# SM3320-BATT-EV.net
KiCad netlist of a schematic drawn in Altium Designer
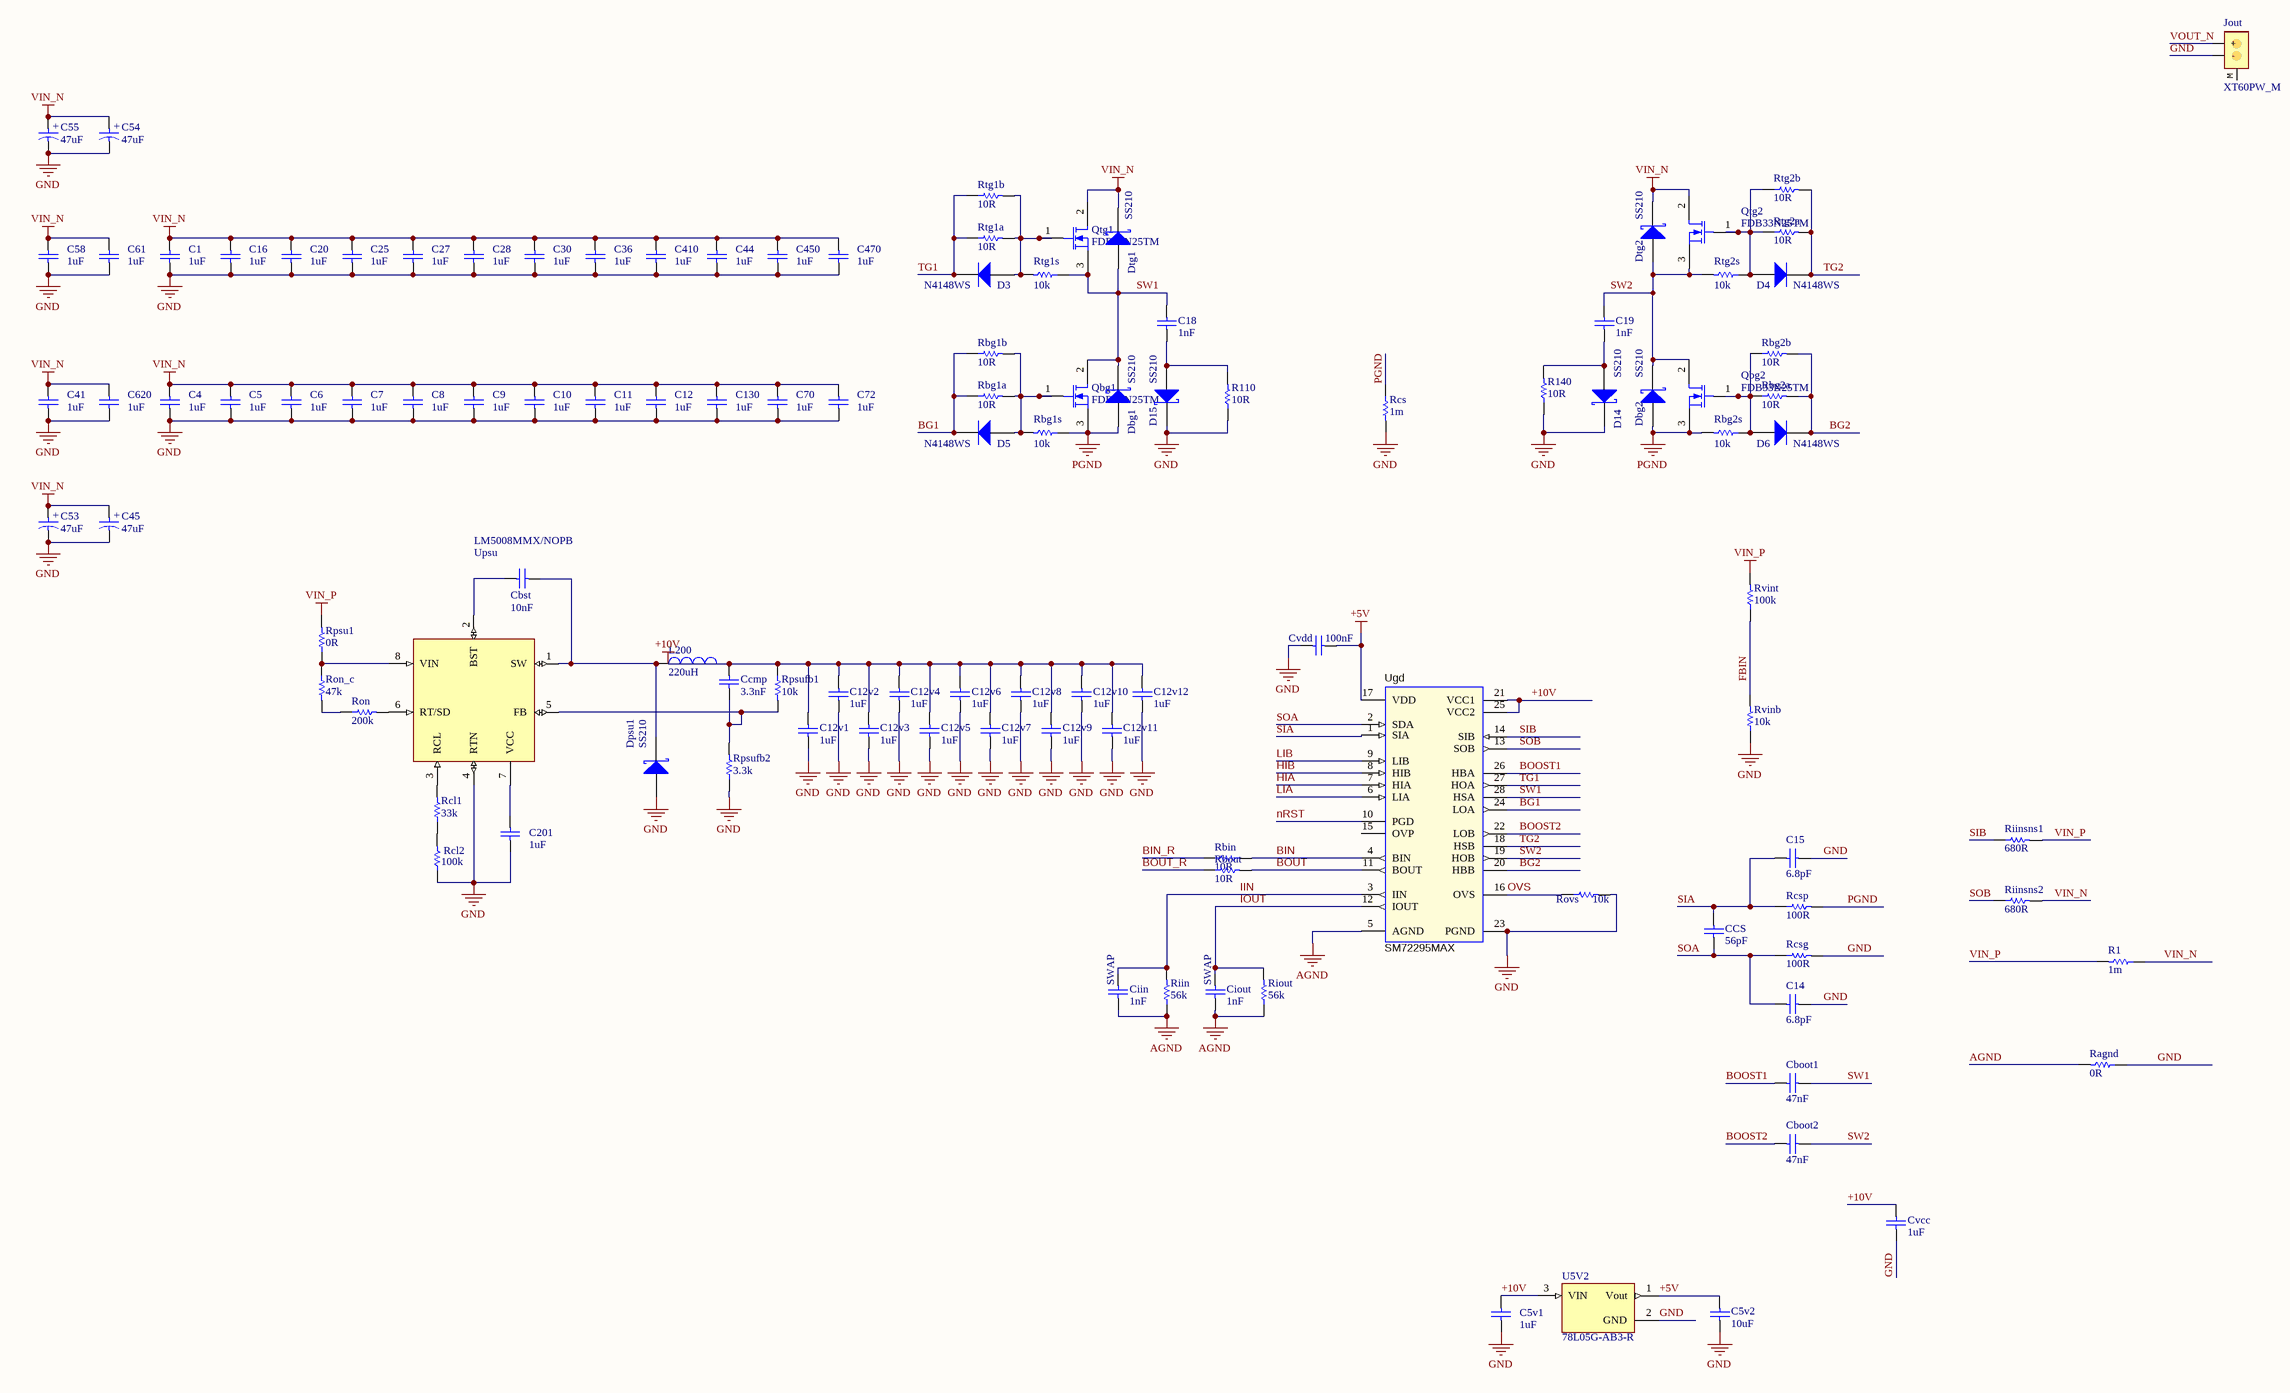
[diagram p0: SM3320-BATT-EV.SchDoc]

(export (version "E")
  (design (tool "Eeschema 10.0.6"))
  (components
    (comp (ref "C1")
      (value "1uF")
      (footprint "C_1206")
      (description "C - CAPACITOR - MLCC - 1uF - 100V - 1206 - X7R")
      (fields (field (name "LCSC PART #") "C91151") (field (name "Comment") "1206B105K101NT"))
      (libsource (lib "JLC_PCB") (part "1206B105K101NT"))
    )
    (comp (ref "C4")
      (value "1uF")
      (footprint "C_1206")
      (description "C - CAPACITOR - MLCC - 1uF - 100V - 1206 - X7R")
      (fields (field (name "LCSC PART #") "C91151") (field (name "Comment") "1206B105K101NT"))
      (libsource (lib "JLC_PCB") (part "1206B105K101NT"))
    )
    (comp (ref "C5")
      (value "1uF")
      (footprint "C_1206")
      (description "C - CAPACITOR - MLCC - 1uF - 100V - 1206 - X7R")
      (fields (field (name "LCSC PART #") "C91151") (field (name "Comment") "1206B105K101NT"))
      (libsource (lib "JLC_PCB") (part "1206B105K101NT"))
    )
    (comp (ref "C5v1")
      (value "1uF")
      (footprint "C_0402")
      (description "C - CAPACITOR - MLCC - 1uF - 25V - 0402")
      (fields (field (name "LCSC PART #") "C52923") (field (name "Comment") "CL05A105KA5NQNC"))
      (libsource (lib "JLC_PCB") (part "CL05A105KA5NQNC"))
    )
    (comp (ref "C5v2")
      (value "10uF")
      (footprint "C_0402")
      (description "C - CAPACITOR - MLCC - 10uF - 6.3V - 0402")
      (fields (field (name "LCSC PART #") "C15525") (field (name "Comment") "CL05A106MQ5NUNC"))
      (libsource (lib "JLC_PCB") (part "CL05A106MQ5NUNC"))
    )
    (comp (ref "C6")
      (value "1uF")
      (footprint "C_1206")
      (description "C - CAPACITOR - MLCC - 1uF - 100V - 1206 - X7R")
      (fields (field (name "LCSC PART #") "C91151") (field (name "Comment") "1206B105K101NT"))
      (libsource (lib "JLC_PCB") (part "1206B105K101NT"))
    )
    (comp (ref "C7")
      (value "1uF")
      (footprint "C_1206")
      (description "C - CAPACITOR - MLCC - 1uF - 100V - 1206 - X7R")
      (fields (field (name "LCSC PART #") "C91151") (field (name "Comment") "1206B105K101NT"))
      (libsource (lib "JLC_PCB") (part "1206B105K101NT"))
    )
    (comp (ref "C8")
      (value "1uF")
      (footprint "C_1206")
      (description "C - CAPACITOR - MLCC - 1uF - 100V - 1206 - X7R")
      (fields (field (name "LCSC PART #") "C91151") (field (name "Comment") "1206B105K101NT"))
      (libsource (lib "JLC_PCB") (part "1206B105K101NT"))
    )
    (comp (ref "C9")
      (value "1uF")
      (footprint "C_1206")
      (description "C - CAPACITOR - MLCC - 1uF - 100V - 1206 - X7R")
      (fields (field (name "LCSC PART #") "C91151") (field (name "Comment") "1206B105K101NT"))
      (libsource (lib "JLC_PCB") (part "1206B105K101NT"))
    )
    (comp (ref "C10")
      (value "1uF")
      (footprint "C_1206")
      (description "C - CAPACITOR - MLCC - 1uF - 100V - 1206 - X7R")
      (fields (field (name "LCSC PART #") "C91151") (field (name "Comment") "1206B105K101NT"))
      (libsource (lib "JLC_PCB") (part "1206B105K101NT"))
    )
    (comp (ref "C11")
      (value "1uF")
      (footprint "C_1206")
      (description "C - CAPACITOR - MLCC - 1uF - 100V - 1206 - X7R")
      (fields (field (name "LCSC PART #") "C91151") (field (name "Comment") "1206B105K101NT"))
      (libsource (lib "JLC_PCB") (part "1206B105K101NT"))
    )
    (comp (ref "C12")
      (value "1uF")
      (footprint "C_1206")
      (description "C - CAPACITOR - MLCC - 1uF - 100V - 1206 - X7R")
      (fields (field (name "LCSC PART #") "C91151") (field (name "Comment") "1206B105K101NT"))
      (libsource (lib "JLC_PCB") (part "1206B105K101NT"))
    )
    (comp (ref "C12v1")
      (value "1uF")
      (footprint "C_0402")
      (description "C - CAPACITOR - MLCC - 1uF - 25V - 0402")
      (fields (field (name "LCSC PART #") "C52923") (field (name "Comment") "CL05A105KA5NQNC"))
      (libsource (lib "JLC_PCB") (part "CL05A105KA5NQNC"))
    )
    (comp (ref "C12v2")
      (value "1uF")
      (footprint "C_0402")
      (description "C - CAPACITOR - MLCC - 1uF - 25V - 0402")
      (fields (field (name "LCSC PART #") "C52923") (field (name "Comment") "CL05A105KA5NQNC"))
      (libsource (lib "JLC_PCB") (part "CL05A105KA5NQNC"))
    )
    (comp (ref "C12v3")
      (value "1uF")
      (footprint "C_0402")
      (description "C - CAPACITOR - MLCC - 1uF - 25V - 0402")
      (fields (field (name "LCSC PART #") "C52923") (field (name "Comment") "CL05A105KA5NQNC"))
      (libsource (lib "JLC_PCB") (part "CL05A105KA5NQNC"))
    )
    (comp (ref "C12v4")
      (value "1uF")
      (footprint "C_0402")
      (description "C - CAPACITOR - MLCC - 1uF - 25V - 0402")
      (fields (field (name "LCSC PART #") "C52923") (field (name "Comment") "CL05A105KA5NQNC"))
      (libsource (lib "JLC_PCB") (part "CL05A105KA5NQNC"))
    )
    (comp (ref "C12v5")
      (value "1uF")
      (footprint "C_0402")
      (description "C - CAPACITOR - MLCC - 1uF - 25V - 0402")
      (fields (field (name "LCSC PART #") "C52923") (field (name "Comment") "CL05A105KA5NQNC"))
      (libsource (lib "JLC_PCB") (part "CL05A105KA5NQNC"))
    )
    (comp (ref "C12v6")
      (value "1uF")
      (footprint "C_0402")
      (description "C - CAPACITOR - MLCC - 1uF - 25V - 0402")
      (fields (field (name "LCSC PART #") "C52923") (field (name "Comment") "CL05A105KA5NQNC"))
      (libsource (lib "JLC_PCB") (part "CL05A105KA5NQNC"))
    )
    (comp (ref "C12v7")
      (value "1uF")
      (footprint "C_0402")
      (description "C - CAPACITOR - MLCC - 1uF - 25V - 0402")
      (fields (field (name "LCSC PART #") "C52923") (field (name "Comment") "CL05A105KA5NQNC"))
      (libsource (lib "JLC_PCB") (part "CL05A105KA5NQNC"))
    )
    (comp (ref "C12v8")
      (value "1uF")
      (footprint "C_0402")
      (description "C - CAPACITOR - MLCC - 1uF - 25V - 0402")
      (fields (field (name "LCSC PART #") "C52923") (field (name "Comment") "CL05A105KA5NQNC"))
      (libsource (lib "JLC_PCB") (part "CL05A105KA5NQNC"))
    )
    (comp (ref "C12v9")
      (value "1uF")
      (footprint "C_0402")
      (description "C - CAPACITOR - MLCC - 1uF - 25V - 0402")
      (fields (field (name "LCSC PART #") "C52923") (field (name "Comment") "CL05A105KA5NQNC"))
      (libsource (lib "JLC_PCB") (part "CL05A105KA5NQNC"))
    )
    (comp (ref "C12v10")
      (value "1uF")
      (footprint "C_0402")
      (description "C - CAPACITOR - MLCC - 1uF - 25V - 0402")
      (fields (field (name "LCSC PART #") "C52923") (field (name "Comment") "CL05A105KA5NQNC"))
      (libsource (lib "JLC_PCB") (part "CL05A105KA5NQNC"))
    )
    (comp (ref "C12v11")
      (value "1uF")
      (footprint "C_0402")
      (description "C - CAPACITOR - MLCC - 1uF - 25V - 0402")
      (fields (field (name "LCSC PART #") "C52923") (field (name "Comment") "CL05A105KA5NQNC"))
      (libsource (lib "JLC_PCB") (part "CL05A105KA5NQNC"))
    )
    (comp (ref "C12v12")
      (value "1uF")
      (footprint "C_0402")
      (description "C - CAPACITOR - MLCC - 1uF - 25V - 0402")
      (fields (field (name "LCSC PART #") "C52923") (field (name "Comment") "CL05A105KA5NQNC"))
      (libsource (lib "JLC_PCB") (part "CL05A105KA5NQNC"))
    )
    (comp (ref "C14")
      (value "6.8pF")
      (footprint "C_0402")
      (description "C - CAPACITOR - MLCC - 6.8pF - 50V - 0402")
      (fields (field (name "LCSC PART #") "C1576") (field (name "Comment") "0402CG6R8C500NT"))
      (libsource (lib "JLC_PCB") (part "0402CG6R8C500NT"))
    )
    (comp (ref "C15")
      (value "6.8pF")
      (footprint "C_0402")
      (description "C - CAPACITOR - MLCC - 6.8pF - 50V - 0402")
      (fields (field (name "LCSC PART #") "C1576") (field (name "Comment") "0402CG6R8C500NT"))
      (libsource (lib "JLC_PCB") (part "0402CG6R8C500NT"))
    )
    (comp (ref "C16")
      (value "1uF")
      (footprint "C_1206")
      (description "C - CAPACITOR - MLCC - 1uF - 100V - 1206 - X7R")
      (fields (field (name "LCSC PART #") "C91151") (field (name "Comment") "1206B105K101NT"))
      (libsource (lib "JLC_PCB") (part "1206B105K101NT"))
    )
    (comp (ref "C18")
      (value "1nF")
      (footprint "C_1206")
      (description "C - CAPACITOR - MLCC - 1nF - 2000V - 1206 - X7R")
      (fields (field (name "LCSC PART #") "C9196") (field (name "Comment") "1206B102K202NT"))
      (libsource (lib "JLC_PCB") (part "1206B102K202NT"))
    )
    (comp (ref "C19")
      (value "1nF")
      (footprint "C_1206")
      (description "C - CAPACITOR - MLCC - 1nF - 2000V - 1206 - X7R")
      (fields (field (name "LCSC PART #") "C9196") (field (name "Comment") "1206B102K202NT"))
      (libsource (lib "JLC_PCB") (part "1206B102K202NT"))
    )
    (comp (ref "C20")
      (value "1uF")
      (footprint "C_1206")
      (description "C - CAPACITOR - MLCC - 1uF - 100V - 1206 - X7R")
      (fields (field (name "LCSC PART #") "C91151") (field (name "Comment") "1206B105K101NT"))
      (libsource (lib "JLC_PCB") (part "1206B105K101NT"))
    )
    (comp (ref "C25")
      (value "1uF")
      (footprint "C_1206")
      (description "C - CAPACITOR - MLCC - 1uF - 100V - 1206 - X7R")
      (fields (field (name "LCSC PART #") "C91151") (field (name "Comment") "1206B105K101NT"))
      (libsource (lib "JLC_PCB") (part "1206B105K101NT"))
    )
    (comp (ref "C27")
      (value "1uF")
      (footprint "C_1206")
      (description "C - CAPACITOR - MLCC - 1uF - 100V - 1206 - X7R")
      (fields (field (name "LCSC PART #") "C91151") (field (name "Comment") "1206B105K101NT"))
      (libsource (lib "JLC_PCB") (part "1206B105K101NT"))
    )
    (comp (ref "C28")
      (value "1uF")
      (footprint "C_1206")
      (description "C - CAPACITOR - MLCC - 1uF - 100V - 1206 - X7R")
      (fields (field (name "LCSC PART #") "C91151") (field (name "Comment") "1206B105K101NT"))
      (libsource (lib "JLC_PCB") (part "1206B105K101NT"))
    )
    (comp (ref "C30")
      (value "1uF")
      (footprint "C_1206")
      (description "C - CAPACITOR - MLCC - 1uF - 100V - 1206 - X7R")
      (fields (field (name "LCSC PART #") "C91151") (field (name "Comment") "1206B105K101NT"))
      (libsource (lib "JLC_PCB") (part "1206B105K101NT"))
    )
    (comp (ref "C36")
      (value "1uF")
      (footprint "C_1206")
      (description "C - CAPACITOR - MLCC - 1uF - 100V - 1206 - X7R")
      (fields (field (name "LCSC PART #") "C91151") (field (name "Comment") "1206B105K101NT"))
      (libsource (lib "JLC_PCB") (part "1206B105K101NT"))
    )
    (comp (ref "C41")
      (value "1uF")
      (footprint "C_1206")
      (description "C - CAPACITOR - MLCC - 1uF - 100V - 1206 - X7R")
      (fields (field (name "LCSC PART #") "C91151") (field (name "Comment") "1206B105K101NT"))
      (libsource (lib "JLC_PCB") (part "1206B105K101NT"))
    )
    (comp (ref "C44")
      (value "1uF")
      (footprint "C_1206")
      (description "C - CAPACITOR - MLCC - 1uF - 100V - 1206 - X7R")
      (fields (field (name "LCSC PART #") "C91151") (field (name "Comment") "1206B105K101NT"))
      (libsource (lib "JLC_PCB") (part "1206B105K101NT"))
    )
    (comp (ref "C45")
      (value "47uF")
      (footprint "C_CAN_1010")
      (description "C - CAPACITOR - ELECTROLYTIC - 47uF - 100V")
      (fields (field (name "LCSC PART #") "C164068") (field (name "Comment") "VZH470M2ATR-1010"))
      (libsource (lib "JLC_PCB") (part "VZH470M2ATR-1010"))
    )
    (comp (ref "C53")
      (value "47uF")
      (footprint "C_CAN_1010")
      (description "C - CAPACITOR - ELECTROLYTIC - 47uF - 100V")
      (fields (field (name "LCSC PART #") "C164068") (field (name "Comment") "VZH470M2ATR-1010"))
      (libsource (lib "JLC_PCB") (part "VZH470M2ATR-1010"))
    )
    (comp (ref "C54")
      (value "47uF")
      (footprint "C_CAN_1010")
      (description "C - CAPACITOR - ELECTROLYTIC - 47uF - 100V")
      (fields (field (name "LCSC PART #") "C164068") (field (name "Comment") "VZH470M2ATR-1010"))
      (libsource (lib "JLC_PCB") (part "VZH470M2ATR-1010"))
    )
    (comp (ref "C55")
      (value "47uF")
      (footprint "C_CAN_1010")
      (description "C - CAPACITOR - ELECTROLYTIC - 47uF - 100V")
      (fields (field (name "LCSC PART #") "C164068") (field (name "Comment") "VZH470M2ATR-1010"))
      (libsource (lib "JLC_PCB") (part "VZH470M2ATR-1010"))
    )
    (comp (ref "C58")
      (value "1uF")
      (footprint "C_1206")
      (description "C - CAPACITOR - MLCC - 1uF - 100V - 1206 - X7R")
      (fields (field (name "LCSC PART #") "C91151") (field (name "Comment") "1206B105K101NT"))
      (libsource (lib "JLC_PCB") (part "1206B105K101NT"))
    )
    (comp (ref "C61")
      (value "1uF")
      (footprint "C_1206")
      (description "C - CAPACITOR - MLCC - 1uF - 100V - 1206 - X7R")
      (fields (field (name "LCSC PART #") "C91151") (field (name "Comment") "1206B105K101NT"))
      (libsource (lib "JLC_PCB") (part "1206B105K101NT"))
    )
    (comp (ref "C70")
      (value "1uF")
      (footprint "C_1206")
      (description "C - CAPACITOR - MLCC - 1uF - 100V - 1206 - X7R")
      (fields (field (name "LCSC PART #") "C91151") (field (name "Comment") "1206B105K101NT"))
      (libsource (lib "JLC_PCB") (part "1206B105K101NT"))
    )
    (comp (ref "C72")
      (value "1uF")
      (footprint "C_1206")
      (description "C - CAPACITOR - MLCC - 1uF - 100V - 1206 - X7R")
      (fields (field (name "LCSC PART #") "C91151") (field (name "Comment") "1206B105K101NT"))
      (libsource (lib "JLC_PCB") (part "1206B105K101NT"))
    )
    (comp (ref "C130")
      (value "1uF")
      (footprint "C_1206")
      (description "C - CAPACITOR - MLCC - 1uF - 100V - 1206 - X7R")
      (fields (field (name "LCSC PART #") "C91151") (field (name "Comment") "1206B105K101NT"))
      (libsource (lib "JLC_PCB") (part "1206B105K101NT"))
    )
    (comp (ref "C201")
      (value "1uF")
      (footprint "C_0402")
      (description "C - CAPACITOR - MLCC - 1uF - 25V - 0402")
      (fields (field (name "LCSC PART #") "C52923") (field (name "Comment") "CL05A105KA5NQNC"))
      (libsource (lib "JLC_PCB") (part "CL05A105KA5NQNC"))
    )
    (comp (ref "C410")
      (value "1uF")
      (footprint "C_1206")
      (description "C - CAPACITOR - MLCC - 1uF - 100V - 1206 - X7R")
      (fields (field (name "LCSC PART #") "C91151") (field (name "Comment") "1206B105K101NT"))
      (libsource (lib "JLC_PCB") (part "1206B105K101NT"))
    )
    (comp (ref "C450")
      (value "1uF")
      (footprint "C_1206")
      (description "C - CAPACITOR - MLCC - 1uF - 100V - 1206 - X7R")
      (fields (field (name "LCSC PART #") "C91151") (field (name "Comment") "1206B105K101NT"))
      (libsource (lib "JLC_PCB") (part "1206B105K101NT"))
    )
    (comp (ref "C470")
      (value "1uF")
      (footprint "C_1206")
      (description "C - CAPACITOR - MLCC - 1uF - 100V - 1206 - X7R")
      (fields (field (name "LCSC PART #") "C91151") (field (name "Comment") "1206B105K101NT"))
      (libsource (lib "JLC_PCB") (part "1206B105K101NT"))
    )
    (comp (ref "C620")
      (value "1uF")
      (footprint "C_1206")
      (description "C - CAPACITOR - MLCC - 1uF - 100V - 1206 - X7R")
      (fields (field (name "LCSC PART #") "C91151") (field (name "Comment") "1206B105K101NT"))
      (libsource (lib "JLC_PCB") (part "1206B105K101NT"))
    )
    (comp (ref "Cboot1")
      (value "47nF")
      (footprint "C_0603")
      (description "C - CAPACITOR - MLCC - 470nF - 25V - 0603")
      (fields (field (name "LCSC PART #") "C1623") (field (name "Comment") "CL10B474KA8NNNC"))
      (libsource (lib "JLC_PCB") (part "CL10B474KA8NNNC"))
    )
    (comp (ref "Cboot2")
      (value "47nF")
      (footprint "C_0603")
      (description "C - CAPACITOR - MLCC - 470nF - 25V - 0603")
      (fields (field (name "LCSC PART #") "C1623") (field (name "Comment") "CL10B474KA8NNNC"))
      (libsource (lib "JLC_PCB") (part "CL10B474KA8NNNC"))
    )
    (comp (ref "Cbst")
      (value "10nF")
      (footprint "C_0402")
      (description "C - CAPACITOR - MLCC - 10nF - 50V - 0402")
      (fields (field (name "LCSC PART #") "C15195") (field (name "Comment") "CL05B103KB5NNNC"))
      (libsource (lib "JLC_PCB") (part "CL05B103KB5NNNC"))
    )
    (comp (ref "Ccmp")
      (value "3.3nF")
      (footprint "C_0402")
      (description "C - CAPACITOR - MLCC - 3.3nF - 50V - 0402")
      (fields (field (name "LCSC PART #") "C26404") (field (name "Comment") "CL05B332KB5NNNC"))
      (libsource (lib "JLC_PCB") (part "CL05B332KB5NNNC"))
    )
    (comp (ref "CCS")
      (value "56pF")
      (footprint "C_0402")
      (description "C - CAPACITOR - MLCC - 56pF - 50V -  0402")
      (fields (field (name "LCSC PART #") "C1572") (field (name "Comment") "0402CG560J500NT"))
      (libsource (lib "JLC_PCB") (part "0402CG560J500NT"))
    )
    (comp (ref "Ciin")
      (value "1nF")
      (footprint "C_0402")
      (description "C - CAPACITOR - MLCC - 1nF - 50V - 0402")
      (fields (field (name "LCSC PART #") "C1523") (field (name "Comment") "0402B102K500NT"))
      (libsource (lib "JLC_PCB") (part "0402B102K500NT"))
    )
    (comp (ref "Ciout")
      (value "1nF")
      (footprint "C_0402")
      (description "C - CAPACITOR - MLCC - 1nF - 50V - 0402")
      (fields (field (name "LCSC PART #") "C1523") (field (name "Comment") "0402B102K500NT"))
      (libsource (lib "JLC_PCB") (part "0402B102K500NT"))
    )
    (comp (ref "Cvcc")
      (value "1uF")
      (footprint "C_0402")
      (description "C - CAPACITOR - MLCC - 1uF - 25V - 0402")
      (fields (field (name "LCSC PART #") "C52923") (field (name "Comment") "CL05A105KA5NQNC"))
      (libsource (lib "JLC_PCB") (part "CL05A105KA5NQNC"))
    )
    (comp (ref "Cvdd")
      (value "100nF")
      (footprint "C_0402")
      (description "C - CAPACITOR - MLCC - 100nF - 16V - 0402")
      (fields (field (name "LCSC PART #") "C1525") (field (name "Comment") "CL05B104KO5NNNC"))
      (libsource (lib "JLC_PCB") (part "CL05B104KO5NNNC"))
    )
    (comp (ref "D3")
      (value "N4148WS")
      (footprint "SOD-323")
      (description "D - DIODE - FAST TRR - 100V - 150mA - 4ns")
      (fields (field (name "LCSC PART #") "C2128"))
      (libsource (lib "JLC_PCB") (part "N4148WS"))
    )
    (comp (ref "D4")
      (value "N4148WS")
      (footprint "SOD-323")
      (description "D - DIODE - FAST TRR - 100V - 150mA - 4ns")
      (fields (field (name "LCSC PART #") "C2128"))
      (libsource (lib "JLC_PCB") (part "N4148WS"))
    )
    (comp (ref "D5")
      (value "N4148WS")
      (footprint "SOD-323")
      (description "D - DIODE - FAST TRR - 100V - 150mA - 4ns")
      (fields (field (name "LCSC PART #") "C2128"))
      (libsource (lib "JLC_PCB") (part "N4148WS"))
    )
    (comp (ref "D6")
      (value "N4148WS")
      (footprint "SOD-323")
      (description "D - DIODE - FAST TRR - 100V - 150mA - 4ns")
      (fields (field (name "LCSC PART #") "C2128"))
      (libsource (lib "JLC_PCB") (part "N4148WS"))
    )
    (comp (ref "D14")
      (value "SS210")
      (footprint "DO-214AC")
      (description "D - DIODE - SCHOTTKY - 100V - 2A")
      (fields (field (name "LCSC PART #") "C14996"))
      (libsource (lib "JLC_PCB") (part "SS210"))
    )
    (comp (ref "D15")
      (value "SS210")
      (footprint "DO-214AC")
      (description "D - DIODE - SCHOTTKY - 100V - 2A")
      (fields (field (name "LCSC PART #") "C14996"))
      (libsource (lib "JLC_PCB") (part "SS210"))
    )
    (comp (ref "Dbg1")
      (value "SS210")
      (footprint "DO-214AC")
      (description "D - DIODE - SCHOTTKY - 100V - 2A")
      (fields (field (name "LCSC PART #") "C14996"))
      (libsource (lib "JLC_PCB") (part "SS210"))
    )
    (comp (ref "Dbg2")
      (value "SS210")
      (footprint "DO-214AC")
      (description "D - DIODE - SCHOTTKY - 100V - 2A")
      (fields (field (name "LCSC PART #") "C14996"))
      (libsource (lib "JLC_PCB") (part "SS210"))
    )
    (comp (ref "Dpsu1")
      (value "SS210")
      (footprint "DO-214AC")
      (description "D - DIODE - SCHOTTKY - 100V - 2A")
      (fields (field (name "LCSC PART #") "C14996"))
      (libsource (lib "JLC_PCB") (part "SS210"))
    )
    (comp (ref "Dtg1")
      (value "SS210")
      (footprint "DO-214AC")
      (description "D - DIODE - SCHOTTKY - 100V - 2A")
      (fields (field (name "LCSC PART #") "C14996"))
      (libsource (lib "JLC_PCB") (part "SS210"))
    )
    (comp (ref "Dtg2")
      (value "SS210")
      (footprint "DO-214AC")
      (description "D - DIODE - SCHOTTKY - 100V - 2A")
      (fields (field (name "LCSC PART #") "C14996"))
      (libsource (lib "JLC_PCB") (part "SS210"))
    )
    (comp (ref "Jout")
      (value "XT60PW_M")
      (footprint "XT60PW_M")
      (description "J - JACK - POWER - XT60 - RIGHT - MALE")
      (fields (field (name "LCSC PART #") "X"))
      (libsource (lib "JLC_PCB") (part "XT60PW_M"))
    )
    (comp (ref "L200")
      (value "220uH")
      (footprint "SRR1260")
      (description "L - INDUCTOR - 220uH - 1.6A - 12.5mm")
      (fields (field (name "LCSC PART #") "C169380") (field (name "Comment") "SWRB1207S-221MT"))
      (libsource (lib "JLC_PCB") (part "SWRB1207S-221MT"))
    )
    (comp (ref "Qbg1")
      (value "FDB33N25TM")
      (footprint "TO-263-3")
      (description "Q - TRANSISTOR - MOSFET (N) - 250V - 33A - 0.094R")
      (fields (field (name "LCSC PART #") "C241752"))
      (libsource (lib "JLC_PCB") (part "FDB33N25TM"))
    )
    (comp (ref "Qbg2")
      (value "FDB33N25TM")
      (footprint "TO-263-3")
      (description "Q - TRANSISTOR - MOSFET (N) - 250V - 33A - 0.094R")
      (fields (field (name "LCSC PART #") "C241752"))
      (libsource (lib "JLC_PCB") (part "FDB33N25TM"))
    )
    (comp (ref "Qtg1")
      (value "FDB33N25TM")
      (footprint "TO-263-3")
      (description "Q - TRANSISTOR - MOSFET (N) - 250V - 33A - 0.094R")
      (fields (field (name "LCSC PART #") "C241752"))
      (libsource (lib "JLC_PCB") (part "FDB33N25TM"))
    )
    (comp (ref "Qtg2")
      (value "FDB33N25TM")
      (footprint "TO-263-3")
      (description "Q - TRANSISTOR - MOSFET (N) - 250V - 33A - 0.094R")
      (fields (field (name "LCSC PART #") "C241752"))
      (libsource (lib "JLC_PCB") (part "FDB33N25TM"))
    )
    (comp (ref "R1")
      (value "1m")
      (footprint "R_2512")
      (description "R - RESISTOR - SMD - 0.005R - 1% - 2512 - 2W")
      (fields (field (name "LCSC PART #") "C371096") (field (name "POWER") "2W"))
      (libsource (lib "JLC_PCB") (part "FMF25FPJR005-LH"))
    )
    (comp (ref "R110")
      (value "10R")
      (footprint "R_1206")
      (description "R - RESISTOR - SMD - 10R - 1% - 1206")
      (fields (field (name "LCSC PART #") "C17903") (field (name "Comment") "1206W4F100JT5E"))
      (libsource (lib "JLC_PCB") (part "1206W4F100JT5E"))
    )
    (comp (ref "R140")
      (value "10R")
      (footprint "R_1206")
      (description "R - RESISTOR - SMD - 10R - 1% - 1206")
      (fields (field (name "LCSC PART #") "C17903") (field (name "Comment") "1206W4F100JT5E"))
      (libsource (lib "JLC_PCB") (part "1206W4F100JT5E"))
    )
    (comp (ref "Ragnd")
      (value "0R")
      (footprint "R_0402")
      (description "R - RESISTOR - SMD - 0R - 1% - 0402")
      (fields (field (name "LCSC PART #") "C17168") (field (name "Comment") "0402WGF0000TCE"))
      (libsource (lib "JLC_PCB") (part "0402WGF0000TCE"))
    )
    (comp (ref "Rbg1a")
      (value "10R")
      (footprint "R_0402")
      (description "R - RESISTOR - SMD - 10R - 1% - 0402")
      (fields (field (name "LCSC PART #") "C25077") (field (name "Comment") "0402WGF100JTCE"))
      (libsource (lib "JLC_PCB") (part "0402WGF100JTCE"))
    )
    (comp (ref "Rbg1b")
      (value "10R")
      (footprint "R_0402")
      (description "R - RESISTOR - SMD - 10R - 1% - 0402")
      (fields (field (name "LCSC PART #") "C25077") (field (name "Comment") "0402WGF100JTCE"))
      (libsource (lib "JLC_PCB") (part "0402WGF100JTCE"))
    )
    (comp (ref "Rbg1s")
      (value "10k")
      (footprint "R_0402")
      (description "R - RESISTOR - SMD - 10k - 1% - 0402")
      (fields (field (name "LCSC PART #") "C25744") (field (name "Comment") "0402WGF1002TCE"))
      (libsource (lib "JLC_PCB") (part "0402WGF1002TCE"))
    )
    (comp (ref "Rbg2a")
      (value "10R")
      (footprint "R_0402")
      (description "R - RESISTOR - SMD - 10R - 1% - 0402")
      (fields (field (name "LCSC PART #") "C25077") (field (name "Comment") "0402WGF100JTCE"))
      (libsource (lib "JLC_PCB") (part "0402WGF100JTCE"))
    )
    (comp (ref "Rbg2b")
      (value "10R")
      (footprint "R_0402")
      (description "R - RESISTOR - SMD - 10R - 1% - 0402")
      (fields (field (name "LCSC PART #") "C25077") (field (name "Comment") "0402WGF100JTCE"))
      (libsource (lib "JLC_PCB") (part "0402WGF100JTCE"))
    )
    (comp (ref "Rbg2s")
      (value "10k")
      (footprint "R_0402")
      (description "R - RESISTOR - SMD - 10k - 1% - 0402")
      (fields (field (name "LCSC PART #") "C25744") (field (name "Comment") "0402WGF1002TCE"))
      (libsource (lib "JLC_PCB") (part "0402WGF1002TCE"))
    )
    (comp (ref "Rbin")
      (value "10R")
      (footprint "R_0402")
      (description "R - RESISTOR - SMD - 10R - 1% - 0402")
      (fields (field (name "LCSC PART #") "C25077") (field (name "Comment") "0402WGF100JTCE"))
      (libsource (lib "JLC_PCB") (part "0402WGF100JTCE"))
    )
    (comp (ref "Rbout")
      (value "10R")
      (footprint "R_0402")
      (description "R - RESISTOR - SMD - 10R - 1% - 0402")
      (fields (field (name "LCSC PART #") "C25077") (field (name "Comment") "0402WGF100JTCE"))
      (libsource (lib "JLC_PCB") (part "0402WGF100JTCE"))
    )
    (comp (ref "Rcl1")
      (value "33k")
      (footprint "R_0402")
      (description "R - RESISTOR - SMD - 33k - 1% - 0402")
      (fields (field (name "LCSC PART #") "C25779") (field (name "Comment") "0402WGF3302TCE"))
      (libsource (lib "JLC_PCB") (part "0402WGF3302TCE"))
    )
    (comp (ref "Rcl2")
      (value "100k")
      (footprint "R_0402")
      (description "R - RESISTOR - SMD - 100k - 1% -  0402")
      (fields (field (name "LCSC PART #") "C25741") (field (name "Comment") "0402WGF1003TCE"))
      (libsource (lib "JLC_PCB") (part "0402WGF1003TCE"))
    )
    (comp (ref "Rcs")
      (value "1m")
      (footprint "R_2512")
      (description "R - RESISTOR - SMD - 0.005R - 1% - 2512 - 2W")
      (fields (field (name "LCSC PART #") "C371096") (field (name "POWER") "2W"))
      (libsource (lib "JLC_PCB") (part "FMF25FPJR005-LH"))
    )
    (comp (ref "Rcsg")
      (value "100R")
      (footprint "R_0402")
      (description "R - RESISTOR - SMD - 100R - 1% - 0402")
      (fields (field (name "LCSC PART #") "C25076") (field (name "Comment") "0402WGF1000TCE"))
      (libsource (lib "JLC_PCB") (part "0402WGF1000TCE"))
    )
    (comp (ref "Rcsp")
      (value "100R")
      (footprint "R_0402")
      (description "R - RESISTOR - SMD - 100R - 1% - 0402")
      (fields (field (name "LCSC PART #") "C25076") (field (name "Comment") "0402WGF1000TCE"))
      (libsource (lib "JLC_PCB") (part "0402WGF1000TCE"))
    )
    (comp (ref "Riin")
      (value "56k")
      (footprint "R_0402")
      (description "R - RESISTOR - SMD - 56k - 1% - 0402")
      (fields (field (name "LCSC PART #") "C25796") (field (name "Comment") "0402WGF5602TCE"))
      (libsource (lib "JLC_PCB") (part "0402WGF5602TCE"))
    )
    (comp (ref "Riinsns1")
      (value "680R")
      (footprint "R_0603")
      (description "R - RESISTOR - SMD - 680R - 1% - 0603")
      (fields (field (name "LCSC PART #") "C23228") (field (name "Comment") "0603WAF6800T5E"))
      (libsource (lib "JLC_PCB") (part "0603WAF6800T5E"))
    )
    (comp (ref "Riinsns2")
      (value "680R")
      (footprint "R_0603")
      (description "R - RESISTOR - SMD - 680R - 1% - 0603")
      (fields (field (name "LCSC PART #") "C23228") (field (name "Comment") "0603WAF6800T5E"))
      (libsource (lib "JLC_PCB") (part "0603WAF6800T5E"))
    )
    (comp (ref "Riout")
      (value "56k")
      (footprint "R_0402")
      (description "R - RESISTOR - SMD - 56k - 1% - 0402")
      (fields (field (name "LCSC PART #") "C25796") (field (name "Comment") "0402WGF5602TCE"))
      (libsource (lib "JLC_PCB") (part "0402WGF5602TCE"))
    )
    (comp (ref "Ron")
      (value "200k")
      (footprint "R_0402")
      (description "R - RESISTOR - SMD - 200k - 1% - 0402")
      (fields (field (name "LCSC PART #") "C25764") (field (name "Comment") "0402WGF2003TCE"))
      (libsource (lib "JLC_PCB") (part "0402WGF2003TCE"))
    )
    (comp (ref "Ron_c")
      (value "47k")
      (footprint "R_0402")
      (description "R - RESISTOR - SMD - 47k - 1% - 0402")
      (fields (field (name "LCSC PART #") "C25792") (field (name "Comment") "0402WGF4702TCE"))
      (libsource (lib "JLC_PCB") (part "0402WGF4702TCE"))
    )
    (comp (ref "Rovs")
      (value "10k")
      (footprint "R_0402")
      (description "R - RESISTOR - SMD - 10k - 1% - 0402")
      (fields (field (name "LCSC PART #") "C25744") (field (name "Comment") "0402WGF1002TCE"))
      (libsource (lib "JLC_PCB") (part "0402WGF1002TCE"))
    )
    (comp (ref "Rpsu1")
      (value "0R")
      (footprint "R_0402")
      (description "R - RESISTOR - SMD - 0R - 1% - 0402")
      (fields (field (name "LCSC PART #") "C17168") (field (name "Comment") "0402WGF0000TCE"))
      (libsource (lib "JLC_PCB") (part "0402WGF0000TCE"))
    )
    (comp (ref "Rpsufb1")
      (value "10k")
      (footprint "R_0402")
      (description "R - RESISTOR - SMD - 10k - 1% - 0402")
      (fields (field (name "LCSC PART #") "C25744") (field (name "Comment") "0402WGF1002TCE"))
      (libsource (lib "JLC_PCB") (part "0402WGF1002TCE"))
    )
    (comp (ref "Rpsufb2")
      (value "3.3k")
      (footprint "R_0402")
      (description "R - RESISTOR - SMD - 3.3k - 1% - 0402")
      (fields (field (name "LCSC PART #") "C25890") (field (name "Comment") "0402WGF3301TCE"))
      (libsource (lib "JLC_PCB") (part "0402WGF3301TCE"))
    )
    (comp (ref "Rtg1a")
      (value "10R")
      (footprint "R_0402")
      (description "R - RESISTOR - SMD - 10R - 1% - 0402")
      (fields (field (name "LCSC PART #") "C25077") (field (name "Comment") "0402WGF100JTCE"))
      (libsource (lib "JLC_PCB") (part "0402WGF100JTCE"))
    )
    (comp (ref "Rtg1b")
      (value "10R")
      (footprint "R_0402")
      (description "R - RESISTOR - SMD - 10R - 1% - 0402")
      (fields (field (name "LCSC PART #") "C25077") (field (name "Comment") "0402WGF100JTCE"))
      (libsource (lib "JLC_PCB") (part "0402WGF100JTCE"))
    )
    (comp (ref "Rtg1s")
      (value "10k")
      (footprint "R_0402")
      (description "R - RESISTOR - SMD - 10k - 1% - 0402")
      (fields (field (name "LCSC PART #") "C25744") (field (name "Comment") "0402WGF1002TCE"))
      (libsource (lib "JLC_PCB") (part "0402WGF1002TCE"))
    )
    (comp (ref "Rtg2a")
      (value "10R")
      (footprint "R_0402")
      (description "R - RESISTOR - SMD - 10R - 1% - 0402")
      (fields (field (name "LCSC PART #") "C25077") (field (name "Comment") "0402WGF100JTCE"))
      (libsource (lib "JLC_PCB") (part "0402WGF100JTCE"))
    )
    (comp (ref "Rtg2b")
      (value "10R")
      (footprint "R_0402")
      (description "R - RESISTOR - SMD - 10R - 1% - 0402")
      (fields (field (name "LCSC PART #") "C25077") (field (name "Comment") "0402WGF100JTCE"))
      (libsource (lib "JLC_PCB") (part "0402WGF100JTCE"))
    )
    (comp (ref "Rtg2s")
      (value "10k")
      (footprint "R_0402")
      (description "R - RESISTOR - SMD - 10k - 1% - 0402")
      (fields (field (name "LCSC PART #") "C25744") (field (name "Comment") "0402WGF1002TCE"))
      (libsource (lib "JLC_PCB") (part "0402WGF1002TCE"))
    )
    (comp (ref "Rvinb")
      (value "10k")
      (footprint "R_0603")
      (description "R - RESISTOR - SMD - 10k - 1% - 0603")
      (fields (field (name "LCSC PART #") "C25804") (field (name "Comment") "0603WAF1002T5E"))
      (libsource (lib "JLC_PCB") (part "0603WAF1002T5E"))
    )
    (comp (ref "Rvint")
      (value "100k")
      (footprint "R_0603")
      (description "R - RESISTOR - SMD - 100k - 1% -  0603")
      (fields (field (name "LCSC PART #") "C22936") (field (name "Comment") "0603WAF100KT5E"))
      (libsource (lib "JLC_PCB") (part "0603WAF100KT5E"))
    )
    (comp (ref "U5V2")
      (value "78L05G-AB3-R")
      (footprint "SOT-223-3")
      (description "U - IC - 5V Power Regulator")
      (fields (field (name "LCSC PART #") "C71136"))
      (libsource (lib "JLC_PCB") (part "78L05G-AB3-R"))
    )
    (comp (ref "Ugd")
      (value "SM72295MAX")
      (footprint "M28B_M")
      (description "Photovoltaic Full Bridge Driver")
      (fields (field (name "MANUFACTURER") "National Semiconductor") (field (name "PARTNUMBER") "SM72295"))
      (libsource (lib "JLC_PCB") (part "SM72295"))
    )
    (comp (ref "Upsu")
      (value "LM5008MMX/NOPB")
      (footprint "SOP65P490X110-8N")
      (description "U - IC - BUCK CONVERTER, ADJUSTABLE, 95V, 350mA")
      (libsource (lib "JLC_PCB") (part "LM5008MMX/NOPB"))
    )
  )
  (nets
    (net (code "1") (name "+5V") (class "Default")
      (node (ref "C5v2") (pin "2") (pinfunction "2_2") (pintype "passive"))
      (node (ref "Cvdd") (pin "2") (pinfunction "2_2") (pintype "passive"))
      (node (ref "U5V2") (pin "1") (pinfunction "Vout_1") (pintype "output"))
      (node (ref "Ugd") (pin "17") (pinfunction "VDD_17") (pintype "power_in"))
    )
    (net (code "2") (name "+10V") (class "Default")
      (node (ref "C12v1") (pin "1") (pinfunction "1_1") (pintype "passive"))
      (node (ref "C12v10") (pin "1") (pinfunction "1_1") (pintype "passive"))
      (node (ref "C12v11") (pin "1") (pinfunction "1_1") (pintype "passive"))
      (node (ref "C12v12") (pin "1") (pinfunction "1_1") (pintype "passive"))
      (node (ref "C12v2") (pin "1") (pinfunction "1_1") (pintype "passive"))
      (node (ref "C12v3") (pin "1") (pinfunction "1_1") (pintype "passive"))
      (node (ref "C12v4") (pin "1") (pinfunction "1_1") (pintype "passive"))
      (node (ref "C12v5") (pin "1") (pinfunction "1_1") (pintype "passive"))
      (node (ref "C12v6") (pin "1") (pinfunction "1_1") (pintype "passive"))
      (node (ref "C12v7") (pin "1") (pinfunction "1_1") (pintype "passive"))
      (node (ref "C12v8") (pin "1") (pinfunction "1_1") (pintype "passive"))
      (node (ref "C12v9") (pin "1") (pinfunction "1_1") (pintype "passive"))
      (node (ref "C5v1") (pin "2") (pinfunction "2_2") (pintype "passive"))
      (node (ref "Ccmp") (pin "2") (pinfunction "2_2") (pintype "passive"))
      (node (ref "Cvcc") (pin "2") (pinfunction "2_2") (pintype "passive"))
      (node (ref "L200") (pin "2") (pinfunction "2_2") (pintype "passive"))
      (node (ref "Rpsufb1") (pin "1") (pinfunction "1_1") (pintype "passive"))
      (node (ref "U5V2") (pin "3") (pinfunction "VIN_3") (pintype "input"))
      (node (ref "Ugd") (pin "21") (pinfunction "VCC1_21") (pintype "power_in"))
      (node (ref "Ugd") (pin "25") (pinfunction "VCC2_25") (pintype "power_in"))
    )
    (net (code "3") (name "/BG1") (class "Default")
      (node (ref "D5") (pin "1") (pinfunction "K_1") (pintype "passive"))
      (node (ref "Rbg1a") (pin "1") (pinfunction "1_1") (pintype "passive"))
      (node (ref "Rbg1b") (pin "1") (pinfunction "1_1") (pintype "passive"))
      (node (ref "Ugd") (pin "24") (pinfunction "LOA_24") (pintype "output"))
    )
    (net (code "4") (name "/BG2") (class "Default")
      (node (ref "D6") (pin "1") (pinfunction "K_1") (pintype "passive"))
      (node (ref "Rbg2a") (pin "2") (pinfunction "2_2") (pintype "passive"))
      (node (ref "Rbg2b") (pin "2") (pinfunction "2_2") (pintype "passive"))
      (node (ref "Ugd") (pin "20") (pinfunction "HBB_20") (pintype "passive"))
    )
    (net (code "5") (name "/BIN") (class "Default")
      (node (ref "Rbin") (pin "2") (pinfunction "2_2") (pintype "passive"))
      (node (ref "Ugd") (pin "4") (pinfunction "BIN_4") (pintype "output"))
    )
    (net (code "6") (name "/BIN_R") (class "Default")
      (node (ref "Rbin") (pin "1") (pinfunction "1_1") (pintype "passive"))
    )
    (net (code "7") (name "/BOOST1") (class "Default")
      (node (ref "Cboot1") (pin "2") (pinfunction "2_2") (pintype "passive"))
      (node (ref "Ugd") (pin "26") (pinfunction "HBA_26") (pintype "passive"))
    )
    (net (code "8") (name "/BOOST2") (class "Default")
      (node (ref "Cboot2") (pin "2") (pinfunction "2_2") (pintype "passive"))
      (node (ref "Ugd") (pin "22") (pinfunction "LOB_22") (pintype "output"))
    )
    (net (code "9") (name "/BOUT") (class "Default")
      (node (ref "Rbout") (pin "2") (pinfunction "2_2") (pintype "passive"))
      (node (ref "Ugd") (pin "11") (pinfunction "BOUT_11") (pintype "output"))
    )
    (net (code "10") (name "/BOUT_R") (class "Default")
      (node (ref "Rbout") (pin "1") (pinfunction "1_1") (pintype "passive"))
    )
    (net (code "11") (name "/FBIN") (class "Default")
      (node (ref "Rvinb") (pin "2") (pinfunction "2_2") (pintype "passive"))
      (node (ref "Rvint") (pin "1") (pinfunction "1_1") (pintype "passive"))
    )
    (net (code "12") (name "/HIA") (class "Default")
      (node (ref "Ugd") (pin "7") (pinfunction "HIA_7") (pintype "input"))
    )
    (net (code "13") (name "/HIB") (class "Default")
      (node (ref "Ugd") (pin "8") (pinfunction "HIB_8") (pintype "input"))
    )
    (net (code "14") (name "/IIN") (class "Default")
      (node (ref "Ciin") (pin "2") (pinfunction "2_2") (pintype "passive"))
      (node (ref "Riin") (pin "2") (pinfunction "2_2") (pintype "passive"))
      (node (ref "Ugd") (pin "3") (pinfunction "IIN_3") (pintype "output"))
    )
    (net (code "15") (name "/IOUT") (class "Default")
      (node (ref "Ciout") (pin "2") (pinfunction "2_2") (pintype "passive"))
      (node (ref "Riout") (pin "2") (pinfunction "2_2") (pintype "passive"))
      (node (ref "Ugd") (pin "12") (pinfunction "IOUT_12") (pintype "output"))
    )
    (net (code "16") (name "/LIA") (class "Default")
      (node (ref "Ugd") (pin "6") (pinfunction "LIA_6") (pintype "input"))
    )
    (net (code "17") (name "/LIB") (class "Default")
      (node (ref "Ugd") (pin "9") (pinfunction "LIB_9") (pintype "input"))
    )
    (net (code "18") (name "/OVS") (class "Default")
      (node (ref "Rovs") (pin "1") (pinfunction "1_1") (pintype "passive"))
      (node (ref "Ugd") (pin "16") (pinfunction "OVS_16") (pintype "passive"))
    )
    (net (code "19") (name "/SIA") (class "Default")
      (node (ref "C15") (pin "1") (pinfunction "1_1") (pintype "passive"))
      (node (ref "CCS") (pin "2") (pinfunction "2_2") (pintype "passive"))
      (node (ref "Rcsp") (pin "1") (pinfunction "1_1") (pintype "passive"))
      (node (ref "Ugd") (pin "1") (pinfunction "SIA_1") (pintype "input"))
    )
    (net (code "20") (name "/SIB") (class "Default")
      (node (ref "Riinsns1") (pin "1") (pinfunction "1_1") (pintype "passive"))
      (node (ref "Ugd") (pin "14") (pinfunction "SIB_14") (pintype "input"))
    )
    (net (code "21") (name "/SOA") (class "Default")
      (node (ref "C14") (pin "1") (pinfunction "1_1") (pintype "passive"))
      (node (ref "CCS") (pin "1") (pinfunction "1_1") (pintype "passive"))
      (node (ref "Rcsg") (pin "1") (pinfunction "1_1") (pintype "passive"))
      (node (ref "Ugd") (pin "2") (pinfunction "SDA_2") (pintype "input"))
    )
    (net (code "22") (name "/SOB") (class "Default")
      (node (ref "Riinsns2") (pin "1") (pinfunction "1_1") (pintype "passive"))
      (node (ref "Ugd") (pin "13") (pinfunction "SOB_13") (pintype "output"))
    )
    (net (code "23") (name "/SW1") (class "Default")
      (node (ref "C18") (pin "2") (pinfunction "2_2") (pintype "passive"))
      (node (ref "Cboot1") (pin "1") (pinfunction "1_1") (pintype "passive"))
      (node (ref "Dbg1") (pin "1") (pinfunction "K_1") (pintype "passive"))
      (node (ref "Dtg1") (pin "2") (pinfunction "A_2") (pintype "passive"))
      (node (ref "Qbg1") (pin "2") (pinfunction "D_2") (pintype "passive"))
      (node (ref "Qtg1") (pin "3") (pinfunction "S_3") (pintype "passive"))
      (node (ref "Rtg1s") (pin "1") (pinfunction "1_1") (pintype "passive"))
      (node (ref "Ugd") (pin "28") (pinfunction "HSA_28") (pintype "passive"))
    )
    (net (code "24") (name "/SW2") (class "Default")
      (node (ref "C19") (pin "2") (pinfunction "2_2") (pintype "passive"))
      (node (ref "Cboot2") (pin "1") (pinfunction "1_1") (pintype "passive"))
      (node (ref "Dbg2") (pin "1") (pinfunction "K_1") (pintype "passive"))
      (node (ref "Dtg2") (pin "2") (pinfunction "A_2") (pintype "passive"))
      (node (ref "Qbg2") (pin "2") (pinfunction "D_2") (pintype "passive"))
      (node (ref "Qtg2") (pin "3") (pinfunction "S_3") (pintype "passive"))
      (node (ref "Rtg2s") (pin "2") (pinfunction "2_2") (pintype "passive"))
      (node (ref "Ugd") (pin "19") (pinfunction "HOB_19") (pintype "output"))
    )
    (net (code "25") (name "/TG1") (class "Default")
      (node (ref "D3") (pin "1") (pinfunction "K_1") (pintype "passive"))
      (node (ref "Rtg1a") (pin "1") (pinfunction "1_1") (pintype "passive"))
      (node (ref "Rtg1b") (pin "1") (pinfunction "1_1") (pintype "passive"))
      (node (ref "Ugd") (pin "27") (pinfunction "HOA_27") (pintype "output"))
    )
    (net (code "26") (name "/TG2") (class "Default")
      (node (ref "D4") (pin "1") (pinfunction "K_1") (pintype "passive"))
      (node (ref "Rtg2a") (pin "2") (pinfunction "2_2") (pintype "passive"))
      (node (ref "Rtg2b") (pin "2") (pinfunction "2_2") (pintype "passive"))
      (node (ref "Ugd") (pin "18") (pinfunction "HSB_18") (pintype "passive"))
    )
    (net (code "27") (name "/VOUT_N") (class "Default")
      (node (ref "Jout") (pin "PLUS") (pinfunction "+_PLUS") (pintype "passive"))
    )
    (net (code "28") (name "/nRST") (class "Default")
      (node (ref "Ugd") (pin "10") (pinfunction "PGD_10") (pintype "open_collector"))
    )
    (net (code "29") (name "AGND") (class "Default")
      (node (ref "Ciin") (pin "1") (pinfunction "1_1") (pintype "passive"))
      (node (ref "Ciout") (pin "1") (pinfunction "1_1") (pintype "passive"))
      (node (ref "Ragnd") (pin "2") (pinfunction "2_2") (pintype "passive"))
      (node (ref "Riin") (pin "1") (pinfunction "1_1") (pintype "passive"))
      (node (ref "Riout") (pin "1") (pinfunction "1_1") (pintype "passive"))
      (node (ref "Ugd") (pin "5") (pinfunction "AGND_5") (pintype "power_in"))
    )
    (net (code "30") (name "GND") (class "Default")
      (node (ref "C1") (pin "1") (pinfunction "1_1") (pintype "passive"))
      (node (ref "C10") (pin "1") (pinfunction "1_1") (pintype "passive"))
      (node (ref "C11") (pin "1") (pinfunction "1_1") (pintype "passive"))
      (node (ref "C12") (pin "1") (pinfunction "1_1") (pintype "passive"))
      (node (ref "C12v1") (pin "2") (pinfunction "2_2") (pintype "passive"))
      (node (ref "C12v10") (pin "2") (pinfunction "2_2") (pintype "passive"))
      (node (ref "C12v11") (pin "2") (pinfunction "2_2") (pintype "passive"))
      (node (ref "C12v12") (pin "2") (pinfunction "2_2") (pintype "passive"))
      (node (ref "C12v2") (pin "2") (pinfunction "2_2") (pintype "passive"))
      (node (ref "C12v3") (pin "2") (pinfunction "2_2") (pintype "passive"))
      (node (ref "C12v4") (pin "2") (pinfunction "2_2") (pintype "passive"))
      (node (ref "C12v5") (pin "2") (pinfunction "2_2") (pintype "passive"))
      (node (ref "C12v6") (pin "2") (pinfunction "2_2") (pintype "passive"))
      (node (ref "C12v7") (pin "2") (pinfunction "2_2") (pintype "passive"))
      (node (ref "C12v8") (pin "2") (pinfunction "2_2") (pintype "passive"))
      (node (ref "C12v9") (pin "2") (pinfunction "2_2") (pintype "passive"))
      (node (ref "C130") (pin "1") (pinfunction "1_1") (pintype "passive"))
      (node (ref "C14") (pin "2") (pinfunction "2_2") (pintype "passive"))
      (node (ref "C15") (pin "2") (pinfunction "2_2") (pintype "passive"))
      (node (ref "C16") (pin "1") (pinfunction "1_1") (pintype "passive"))
      (node (ref "C20") (pin "1") (pinfunction "1_1") (pintype "passive"))
      (node (ref "C201") (pin "2") (pinfunction "2_2") (pintype "passive"))
      (node (ref "C25") (pin "1") (pinfunction "1_1") (pintype "passive"))
      (node (ref "C27") (pin "1") (pinfunction "1_1") (pintype "passive"))
      (node (ref "C28") (pin "1") (pinfunction "1_1") (pintype "passive"))
      (node (ref "C30") (pin "1") (pinfunction "1_1") (pintype "passive"))
      (node (ref "C36") (pin "1") (pinfunction "1_1") (pintype "passive"))
      (node (ref "C4") (pin "1") (pinfunction "1_1") (pintype "passive"))
      (node (ref "C41") (pin "1") (pinfunction "1_1") (pintype "passive"))
      (node (ref "C410") (pin "1") (pinfunction "1_1") (pintype "passive"))
      (node (ref "C44") (pin "1") (pinfunction "1_1") (pintype "passive"))
      (node (ref "C45") (pin "1") (pinfunction "1_1") (pintype "passive"))
      (node (ref "C450") (pin "1") (pinfunction "1_1") (pintype "passive"))
      (node (ref "C470") (pin "1") (pinfunction "1_1") (pintype "passive"))
      (node (ref "C5") (pin "1") (pinfunction "1_1") (pintype "passive"))
      (node (ref "C53") (pin "1") (pinfunction "1_1") (pintype "passive"))
      (node (ref "C54") (pin "1") (pinfunction "1_1") (pintype "passive"))
      (node (ref "C55") (pin "1") (pinfunction "1_1") (pintype "passive"))
      (node (ref "C58") (pin "1") (pinfunction "1_1") (pintype "passive"))
      (node (ref "C5v1") (pin "1") (pinfunction "1_1") (pintype "passive"))
      (node (ref "C5v2") (pin "1") (pinfunction "1_1") (pintype "passive"))
      (node (ref "C6") (pin "1") (pinfunction "1_1") (pintype "passive"))
      (node (ref "C61") (pin "1") (pinfunction "1_1") (pintype "passive"))
      (node (ref "C620") (pin "1") (pinfunction "1_1") (pintype "passive"))
      (node (ref "C7") (pin "1") (pinfunction "1_1") (pintype "passive"))
      (node (ref "C70") (pin "1") (pinfunction "1_1") (pintype "passive"))
      (node (ref "C72") (pin "1") (pinfunction "1_1") (pintype "passive"))
      (node (ref "C8") (pin "1") (pinfunction "1_1") (pintype "passive"))
      (node (ref "C9") (pin "1") (pinfunction "1_1") (pintype "passive"))
      (node (ref "Cvcc") (pin "1") (pinfunction "1_1") (pintype "passive"))
      (node (ref "Cvdd") (pin "1") (pinfunction "1_1") (pintype "passive"))
      (node (ref "D14") (pin "1") (pinfunction "K_1") (pintype "passive"))
      (node (ref "D15") (pin "1") (pinfunction "K_1") (pintype "passive"))
      (node (ref "Dpsu1") (pin "2") (pinfunction "A_2") (pintype "passive"))
      (node (ref "Jout") (pin "MINUS") (pinfunction "-_MINUS") (pintype "passive"))
      (node (ref "R110") (pin "1") (pinfunction "1_1") (pintype "passive"))
      (node (ref "R140") (pin "1") (pinfunction "1_1") (pintype "passive"))
      (node (ref "Ragnd") (pin "1") (pinfunction "1_1") (pintype "passive"))
      (node (ref "Rcl2") (pin "1") (pinfunction "1_1") (pintype "passive"))
      (node (ref "Rcs") (pin "2") (pinfunction "2_2") (pintype "passive"))
      (node (ref "Rcsg") (pin "2") (pinfunction "2_2") (pintype "passive"))
      (node (ref "Rovs") (pin "2") (pinfunction "2_2") (pintype "passive"))
      (node (ref "Rpsufb2") (pin "1") (pinfunction "1_1") (pintype "passive"))
      (node (ref "Rvinb") (pin "1") (pinfunction "1_1") (pintype "passive"))
      (node (ref "U5V2") (pin "2") (pinfunction "GND_2") (pintype "power_in"))
      (node (ref "Ugd") (pin "23") (pinfunction "PGND_23") (pintype "power_in"))
      (node (ref "Upsu") (pin "4") (pinfunction "RTN_4") (pintype "bidirectional"))
    )
    (net (code "31") (name "Net-(D3-A)") (class "Default")
      (node (ref "D3") (pin "2") (pinfunction "A_2") (pintype "passive"))
      (node (ref "Qtg1") (pin "1") (pinfunction "G_1") (pintype "passive"))
      (node (ref "Rtg1a") (pin "2") (pinfunction "2_2") (pintype "passive"))
      (node (ref "Rtg1b") (pin "2") (pinfunction "2_2") (pintype "passive"))
      (node (ref "Rtg1s") (pin "2") (pinfunction "2_2") (pintype "passive"))
    )
    (net (code "32") (name "Net-(D4-A)") (class "Default")
      (node (ref "D4") (pin "2") (pinfunction "A_2") (pintype "passive"))
      (node (ref "Qtg2") (pin "1") (pinfunction "G_1") (pintype "passive"))
      (node (ref "Rtg2a") (pin "1") (pinfunction "1_1") (pintype "passive"))
      (node (ref "Rtg2b") (pin "1") (pinfunction "1_1") (pintype "passive"))
      (node (ref "Rtg2s") (pin "1") (pinfunction "1_1") (pintype "passive"))
    )
    (net (code "33") (name "Net-(D5-A)") (class "Default")
      (node (ref "D5") (pin "2") (pinfunction "A_2") (pintype "passive"))
      (node (ref "Qbg1") (pin "1") (pinfunction "G_1") (pintype "passive"))
      (node (ref "Rbg1a") (pin "2") (pinfunction "2_2") (pintype "passive"))
      (node (ref "Rbg1b") (pin "2") (pinfunction "2_2") (pintype "passive"))
      (node (ref "Rbg1s") (pin "2") (pinfunction "2_2") (pintype "passive"))
    )
    (net (code "34") (name "Net-(D6-A)") (class "Default")
      (node (ref "D6") (pin "2") (pinfunction "A_2") (pintype "passive"))
      (node (ref "Qbg2") (pin "1") (pinfunction "G_1") (pintype "passive"))
      (node (ref "Rbg2a") (pin "1") (pinfunction "1_1") (pintype "passive"))
      (node (ref "Rbg2b") (pin "1") (pinfunction "1_1") (pintype "passive"))
      (node (ref "Rbg2s") (pin "1") (pinfunction "1_1") (pintype "passive"))
    )
    (net (code "35") (name "Net-(D14-A)") (class "Default")
      (node (ref "C19") (pin "1") (pinfunction "1_1") (pintype "passive"))
      (node (ref "D14") (pin "2") (pinfunction "A_2") (pintype "passive"))
      (node (ref "R140") (pin "2") (pinfunction "2_2") (pintype "passive"))
    )
    (net (code "36") (name "Net-(D15-A)") (class "Default")
      (node (ref "C18") (pin "1") (pinfunction "1_1") (pintype "passive"))
      (node (ref "D15") (pin "2") (pinfunction "A_2") (pintype "passive"))
      (node (ref "R110") (pin "2") (pinfunction "2_2") (pintype "passive"))
    )
    (net (code "37") (name "Net-(Dpsu1-K)") (class "Default")
      (node (ref "Cbst") (pin "2") (pinfunction "2_2") (pintype "passive"))
      (node (ref "Dpsu1") (pin "1") (pinfunction "K_1") (pintype "passive"))
      (node (ref "L200") (pin "1") (pinfunction "1_1") (pintype "passive"))
      (node (ref "Upsu") (pin "1") (pinfunction "SW_1") (pintype "bidirectional"))
    )
    (net (code "38") (name "Net-(Rcl1-Pad1)") (class "Default")
      (node (ref "Rcl1") (pin "1") (pinfunction "1_1") (pintype "passive"))
      (node (ref "Rcl2") (pin "2") (pinfunction "2_2") (pintype "passive"))
    )
    (net (code "39") (name "Net-(Ron-Pad1)") (class "Default")
      (node (ref "Ron") (pin "1") (pinfunction "1_1") (pintype "passive"))
      (node (ref "Ron_c") (pin "2") (pinfunction "2_2") (pintype "passive"))
    )
    (net (code "40") (name "Net-(Upsu-BST)") (class "Default")
      (node (ref "Cbst") (pin "1") (pinfunction "1_1") (pintype "passive"))
      (node (ref "Upsu") (pin "2") (pinfunction "BST_2") (pintype "bidirectional"))
    )
    (net (code "41") (name "Net-(Upsu-FB)") (class "Default")
      (node (ref "Ccmp") (pin "1") (pinfunction "1_1") (pintype "passive"))
      (node (ref "Rpsufb1") (pin "2") (pinfunction "2_2") (pintype "passive"))
      (node (ref "Rpsufb2") (pin "2") (pinfunction "2_2") (pintype "passive"))
      (node (ref "Upsu") (pin "5") (pinfunction "FB_5") (pintype "bidirectional"))
    )
    (net (code "42") (name "Net-(Upsu-RCL)") (class "Default")
      (node (ref "Rcl1") (pin "2") (pinfunction "2_2") (pintype "passive"))
      (node (ref "Upsu") (pin "3") (pinfunction "RCL_3") (pintype "input"))
    )
    (net (code "43") (name "Net-(Upsu-RT{slash}SD)") (class "Default")
      (node (ref "Ron") (pin "2") (pinfunction "2_2") (pintype "passive"))
      (node (ref "Upsu") (pin "6") (pinfunction "RT/SD_6") (pintype "input"))
    )
    (net (code "44") (name "Net-(Upsu-VCC)") (class "Default")
      (node (ref "C201") (pin "1") (pinfunction "1_1") (pintype "passive"))
      (node (ref "Upsu") (pin "7") (pinfunction "VCC_7") (pintype "power_in"))
    )
    (net (code "45") (name "Net-(Upsu-VIN)") (class "Default")
      (node (ref "Ron_c") (pin "1") (pinfunction "1_1") (pintype "passive"))
      (node (ref "Rpsu1") (pin "1") (pinfunction "1_1") (pintype "passive"))
      (node (ref "Upsu") (pin "8") (pinfunction "VIN_8") (pintype "input"))
    )
    (net (code "46") (name "PGND") (class "Default")
      (node (ref "Dbg1") (pin "2") (pinfunction "A_2") (pintype "passive"))
      (node (ref "Dbg2") (pin "2") (pinfunction "A_2") (pintype "passive"))
      (node (ref "Qbg1") (pin "3") (pinfunction "S_3") (pintype "passive"))
      (node (ref "Qbg2") (pin "3") (pinfunction "S_3") (pintype "passive"))
      (node (ref "Rbg1s") (pin "1") (pinfunction "1_1") (pintype "passive"))
      (node (ref "Rbg2s") (pin "2") (pinfunction "2_2") (pintype "passive"))
      (node (ref "Rcs") (pin "1") (pinfunction "1_1") (pintype "passive"))
      (node (ref "Rcsp") (pin "2") (pinfunction "2_2") (pintype "passive"))
    )
    (net (code "47") (name "VIN_N") (class "Default")
      (node (ref "C1") (pin "2") (pinfunction "2_2") (pintype "passive"))
      (node (ref "C10") (pin "2") (pinfunction "2_2") (pintype "passive"))
      (node (ref "C11") (pin "2") (pinfunction "2_2") (pintype "passive"))
      (node (ref "C12") (pin "2") (pinfunction "2_2") (pintype "passive"))
      (node (ref "C130") (pin "2") (pinfunction "2_2") (pintype "passive"))
      (node (ref "C16") (pin "2") (pinfunction "2_2") (pintype "passive"))
      (node (ref "C20") (pin "2") (pinfunction "2_2") (pintype "passive"))
      (node (ref "C25") (pin "2") (pinfunction "2_2") (pintype "passive"))
      (node (ref "C27") (pin "2") (pinfunction "2_2") (pintype "passive"))
      (node (ref "C28") (pin "2") (pinfunction "2_2") (pintype "passive"))
      (node (ref "C30") (pin "2") (pinfunction "2_2") (pintype "passive"))
      (node (ref "C36") (pin "2") (pinfunction "2_2") (pintype "passive"))
      (node (ref "C4") (pin "2") (pinfunction "2_2") (pintype "passive"))
      (node (ref "C41") (pin "2") (pinfunction "2_2") (pintype "passive"))
      (node (ref "C410") (pin "2") (pinfunction "2_2") (pintype "passive"))
      (node (ref "C44") (pin "2") (pinfunction "2_2") (pintype "passive"))
      (node (ref "C45") (pin "2") (pinfunction "2_2") (pintype "passive"))
      (node (ref "C450") (pin "2") (pinfunction "2_2") (pintype "passive"))
      (node (ref "C470") (pin "2") (pinfunction "2_2") (pintype "passive"))
      (node (ref "C5") (pin "2") (pinfunction "2_2") (pintype "passive"))
      (node (ref "C53") (pin "2") (pinfunction "2_2") (pintype "passive"))
      (node (ref "C54") (pin "2") (pinfunction "2_2") (pintype "passive"))
      (node (ref "C55") (pin "2") (pinfunction "2_2") (pintype "passive"))
      (node (ref "C58") (pin "2") (pinfunction "2_2") (pintype "passive"))
      (node (ref "C6") (pin "2") (pinfunction "2_2") (pintype "passive"))
      (node (ref "C61") (pin "2") (pinfunction "2_2") (pintype "passive"))
      (node (ref "C620") (pin "2") (pinfunction "2_2") (pintype "passive"))
      (node (ref "C7") (pin "2") (pinfunction "2_2") (pintype "passive"))
      (node (ref "C70") (pin "2") (pinfunction "2_2") (pintype "passive"))
      (node (ref "C72") (pin "2") (pinfunction "2_2") (pintype "passive"))
      (node (ref "C8") (pin "2") (pinfunction "2_2") (pintype "passive"))
      (node (ref "C9") (pin "2") (pinfunction "2_2") (pintype "passive"))
      (node (ref "Dtg1") (pin "1") (pinfunction "K_1") (pintype "passive"))
      (node (ref "Dtg2") (pin "1") (pinfunction "K_1") (pintype "passive"))
      (node (ref "Qtg1") (pin "2") (pinfunction "D_2") (pintype "passive"))
      (node (ref "Qtg2") (pin "2") (pinfunction "D_2") (pintype "passive"))
      (node (ref "R1") (pin "1") (pinfunction "1_1") (pintype "passive"))
      (node (ref "Riinsns2") (pin "2") (pinfunction "2_2") (pintype "passive"))
    )
    (net (code "48") (name "VIN_P") (class "Default")
      (node (ref "R1") (pin "2") (pinfunction "2_2") (pintype "passive"))
      (node (ref "Riinsns1") (pin "2") (pinfunction "2_2") (pintype "passive"))
      (node (ref "Rpsu1") (pin "2") (pinfunction "2_2") (pintype "passive"))
      (node (ref "Rvint") (pin "2") (pinfunction "2_2") (pintype "passive"))
    )
    (net (code "49") (name "unconnected-(Jout-PadM)") (class "Default")
      (node (ref "Jout") (pin "M") (pinfunction "M_M") (pintype "passive"))
    )
    (net (code "50") (name "unconnected-(Ugd-OVP-Pad15)") (class "Default")
      (node (ref "Ugd") (pin "15") (pinfunction "OVP_15") (pintype "passive"))
    )
  )
)
